# Shruthi-DSP-v03.net
KiCad netlist of a schematic drawn in EAGLE
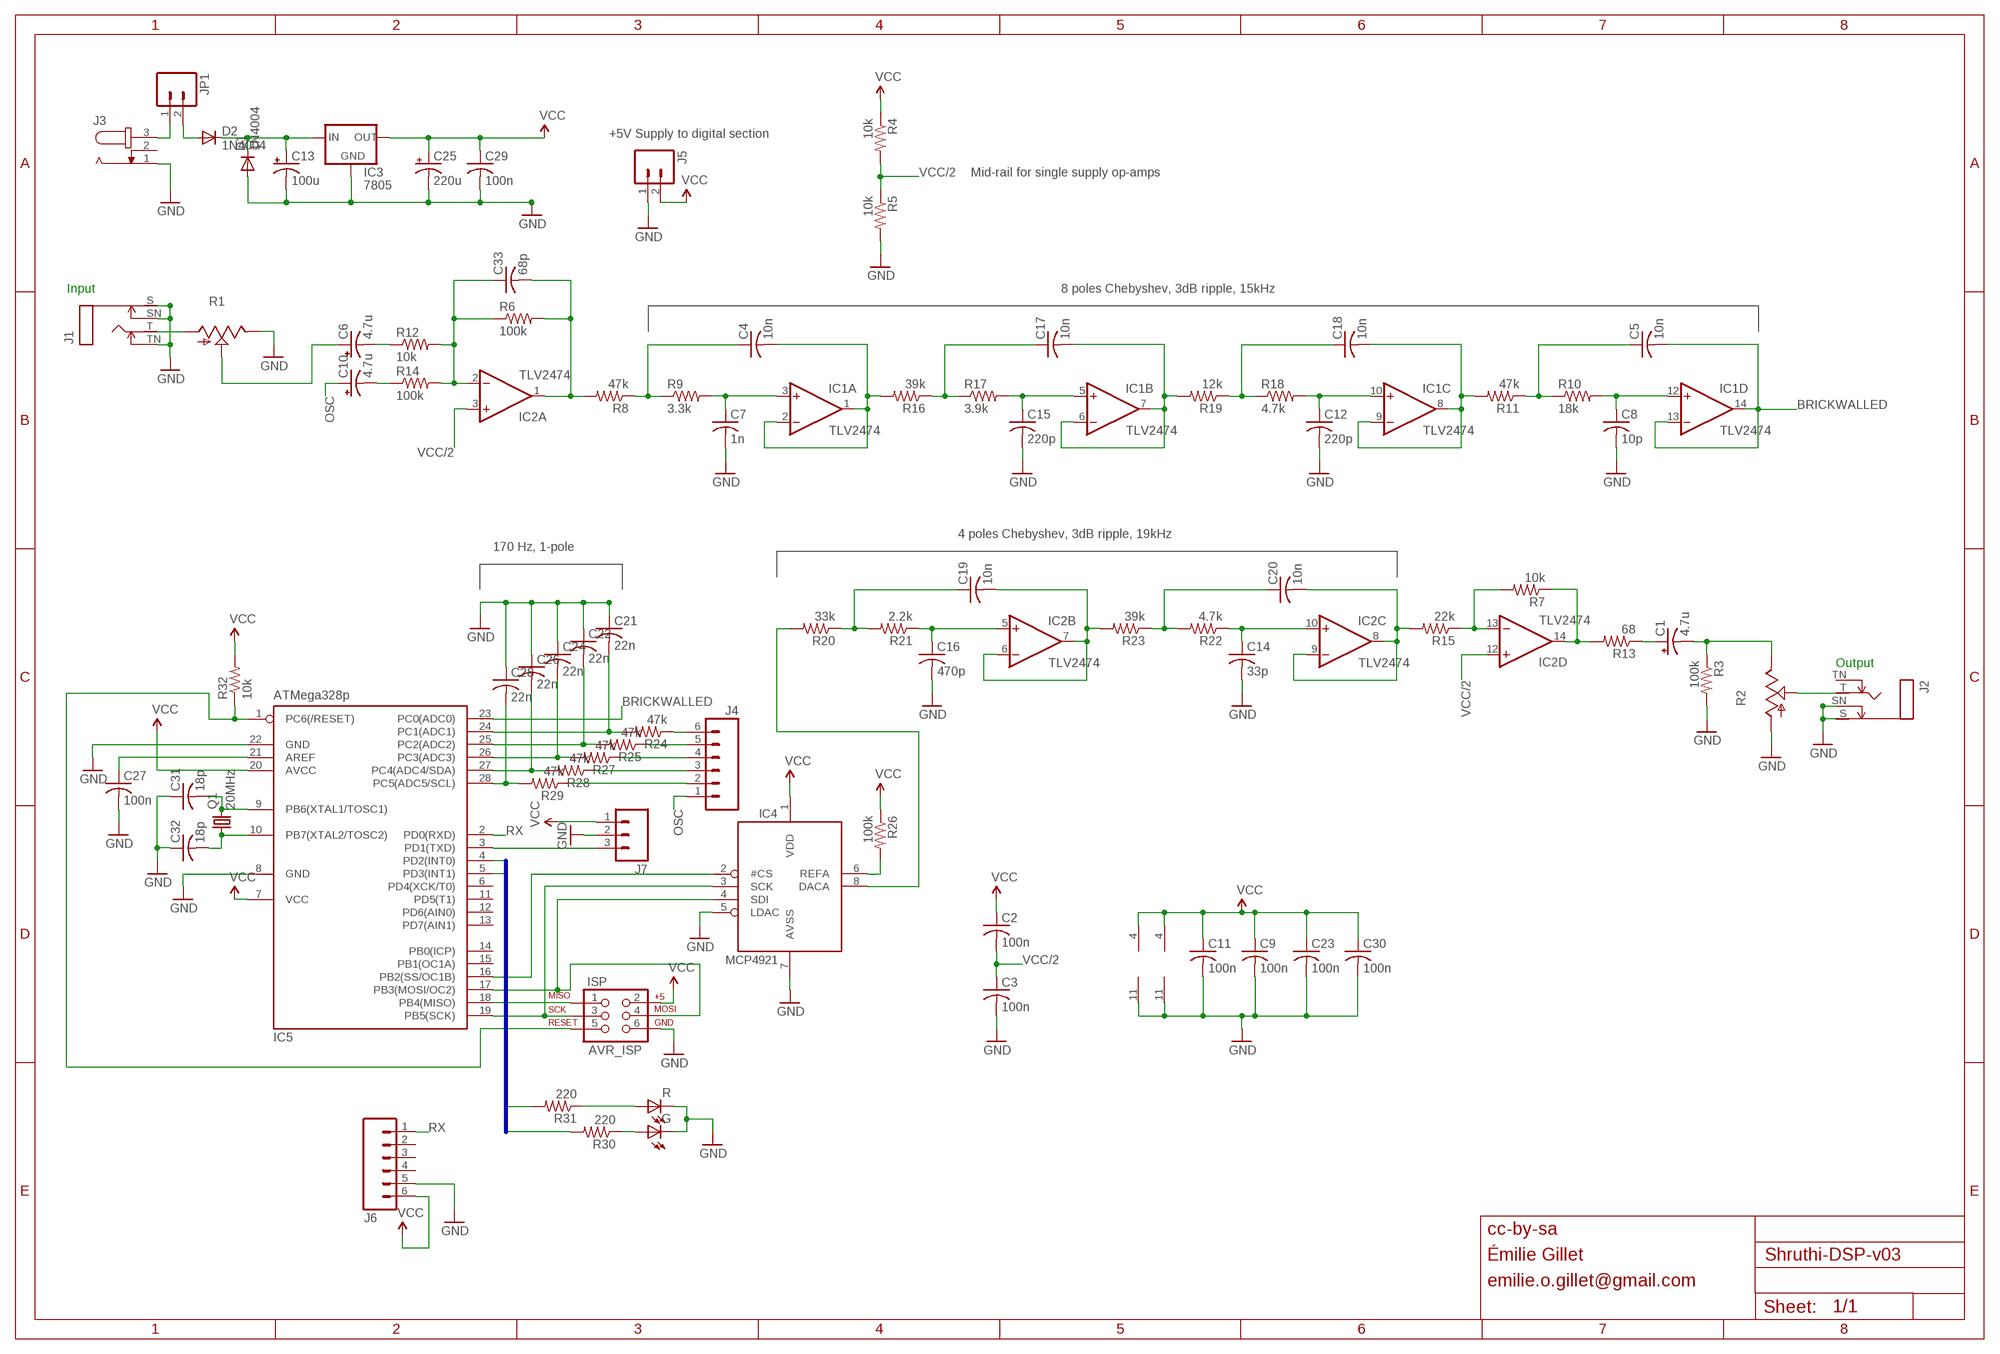
[diagram p0: schematic, sheet 1]

(export (version "E")
  (design (tool "Eeschema 10.0.6"))
  (components
    (comp (ref "C1")
      (value "4.7u")
      (footprint "eagle-import:E2,5-6")
      (libsource (lib "eagle-import") (part "CPOL-USE2.5-6"))
    )
    (comp (ref "C2")
      (value "100n")
      (footprint "eagle-import:C025-024X044")
      (libsource (lib "eagle-import") (part "C-US025-024X044"))
    )
    (comp (ref "C3")
      (value "100n")
      (footprint "eagle-import:C025-024X044")
      (libsource (lib "eagle-import") (part "C-US025-024X044"))
    )
    (comp (ref "C4")
      (value "10n")
      (footprint "eagle-import:C050-025X075")
      (libsource (lib "eagle-import") (part "C-US050-025X075"))
    )
    (comp (ref "C5")
      (value "10n")
      (footprint "eagle-import:C050-025X075")
      (libsource (lib "eagle-import") (part "C-US050-025X075"))
    )
    (comp (ref "C6")
      (value "4.7u")
      (footprint "eagle-import:E2,5-6")
      (libsource (lib "eagle-import") (part "CPOL-USE2.5-6"))
    )
    (comp (ref "C7")
      (value "1n")
      (footprint "eagle-import:C025-025X050")
      (libsource (lib "eagle-import") (part "C-US025-025X050"))
    )
    (comp (ref "C8")
      (value "10p")
      (footprint "eagle-import:C025-025X050")
      (libsource (lib "eagle-import") (part "C-US025-025X050"))
    )
    (comp (ref "C9")
      (value "100n")
      (footprint "eagle-import:C025-025X050")
      (libsource (lib "eagle-import") (part "C-US025-025X050"))
    )
    (comp (ref "C10")
      (value "4.7u")
      (footprint "eagle-import:E2,5-6")
      (libsource (lib "eagle-import") (part "CPOL-USE2.5-6"))
    )
    (comp (ref "C11")
      (value "100n")
      (footprint "eagle-import:C025-025X050")
      (libsource (lib "eagle-import") (part "C-US025-025X050"))
    )
    (comp (ref "C12")
      (value "220p")
      (footprint "eagle-import:C025-025X050")
      (libsource (lib "eagle-import") (part "C-US025-025X050"))
    )
    (comp (ref "C13")
      (value "100u")
      (footprint "eagle-import:E2,5-7")
      (libsource (lib "eagle-import") (part "CPOL-USE2.5-7"))
    )
    (comp (ref "C14")
      (value "33p")
      (footprint "eagle-import:C025-025X050")
      (libsource (lib "eagle-import") (part "C-US025-025X050"))
    )
    (comp (ref "C15")
      (value "220p")
      (footprint "eagle-import:C025-025X050")
      (libsource (lib "eagle-import") (part "C-US025-025X050"))
    )
    (comp (ref "C16")
      (value "470p")
      (footprint "eagle-import:C025-025X050")
      (libsource (lib "eagle-import") (part "C-US025-025X050"))
    )
    (comp (ref "C17")
      (value "10n")
      (footprint "eagle-import:C050-025X075")
      (libsource (lib "eagle-import") (part "C-US050-025X075"))
    )
    (comp (ref "C18")
      (value "10n")
      (footprint "eagle-import:C050-025X075")
      (libsource (lib "eagle-import") (part "C-US050-025X075"))
    )
    (comp (ref "C19")
      (value "10n")
      (footprint "eagle-import:C050-025X075")
      (libsource (lib "eagle-import") (part "C-US050-025X075"))
    )
    (comp (ref "C20")
      (value "10n")
      (footprint "eagle-import:C050-025X075")
      (libsource (lib "eagle-import") (part "C-US050-025X075"))
    )
    (comp (ref "C21")
      (value "22n")
      (footprint "eagle-import:C050-025X075")
      (libsource (lib "eagle-import") (part "C-US050-025X075"))
    )
    (comp (ref "C22")
      (value "22n")
      (footprint "eagle-import:C050-025X075")
      (libsource (lib "eagle-import") (part "C-US050-025X075"))
    )
    (comp (ref "C23")
      (value "100n")
      (footprint "eagle-import:C025-025X050")
      (libsource (lib "eagle-import") (part "C-US025-025X050"))
    )
    (comp (ref "C24")
      (value "22n")
      (footprint "eagle-import:C050-025X075")
      (libsource (lib "eagle-import") (part "C-US050-025X075"))
    )
    (comp (ref "C25")
      (value "220u")
      (footprint "eagle-import:E5-10,5")
      (libsource (lib "eagle-import") (part "CPOL-USE5-10.5"))
    )
    (comp (ref "C26")
      (value "22n")
      (footprint "eagle-import:C050-025X075")
      (libsource (lib "eagle-import") (part "C-US050-025X075"))
    )
    (comp (ref "C27")
      (value "100n")
      (footprint "eagle-import:C025-025X050")
      (libsource (lib "eagle-import") (part "C-US025-025X050"))
    )
    (comp (ref "C28")
      (value "22n")
      (footprint "eagle-import:C050-025X075")
      (libsource (lib "eagle-import") (part "C-US050-025X075"))
    )
    (comp (ref "C29")
      (value "100n")
      (footprint "eagle-import:C025-025X050")
      (libsource (lib "eagle-import") (part "C-US025-025X050"))
    )
    (comp (ref "C30")
      (value "100n")
      (footprint "eagle-import:C025-024X044")
      (libsource (lib "eagle-import") (part "C-US025-024X044"))
    )
    (comp (ref "C31")
      (value "18p")
      (footprint "eagle-import:C025-024X044")
      (libsource (lib "eagle-import") (part "C-US025-024X044"))
    )
    (comp (ref "C32")
      (value "18p")
      (footprint "eagle-import:C025-024X044")
      (libsource (lib "eagle-import") (part "C-US025-024X044"))
    )
    (comp (ref "C33")
      (value "68p")
      (footprint "eagle-import:C025-025X050")
      (libsource (lib "eagle-import") (part "C-US025-025X050"))
    )
    (comp (ref "D1")
      (value "1N4004")
      (footprint "eagle-import:DO41-10")
      (libsource (lib "eagle-import") (part "1N4004"))
    )
    (comp (ref "D2")
      (value "1N4004")
      (footprint "eagle-import:DO41-10")
      (libsource (lib "eagle-import") (part "1N4004"))
    )
    (comp (ref "G")
      (value "LED3MM")
      (footprint "eagle-import:LED3MM")
      (libsource (lib "eagle-import") (part "LED3MM"))
    )
    (comp (ref "IC1")
      (value "TLV2474")
      (footprint "eagle-import:DIL14")
      (libsource (lib "eagle-import") (part "TL084P"))
    )
    (comp (ref "IC2")
      (value "TLV2474")
      (footprint "eagle-import:DIL14")
      (libsource (lib "eagle-import") (part "TL084P"))
    )
    (comp (ref "IC3")
      (value "7805")
      (footprint "eagle-import:78XXS")
      (libsource (lib "eagle-import") (part "78XXS"))
    )
    (comp (ref "IC4")
      (value "MCP4921")
      (footprint "eagle-import:DIL08")
      (libsource (lib "eagle-import") (part "MCP4921"))
    )
    (comp (ref "IC5")
      (value "ATMega328p")
      (footprint "eagle-import:DIL28-3")
      (libsource (lib "eagle-import") (part "MEGA8-P"))
    )
    (comp (ref "ISP")
      (value "AVR_ISP")
      (footprint "eagle-import:2X3")
      (libsource (lib "eagle-import") (part "AVR_SPI_PRG_6PTH"))
    )
    (comp (ref "J1")
      (value "MONOSWS")
      (footprint "eagle-import:NMJ4HC-S")
      (libsource (lib "eagle-import") (part "MONOSWS"))
    )
    (comp (ref "J2")
      (value "MONOSWS")
      (footprint "eagle-import:NMJ4HC-S")
      (libsource (lib "eagle-import") (part "MONOSWS"))
    )
    (comp (ref "J3")
      (value "JACK-PLUG2")
      (footprint "eagle-import:SPC4078_BIG_HOLES")
      (libsource (lib "eagle-import") (part "JACK-PLUG2"))
    )
    (comp (ref "J4")
      (value "M06SIP")
      (footprint "eagle-import:1X06")
      (libsource (lib "eagle-import") (part "M06SIP"))
    )
    (comp (ref "J5")
      (value "M02PTH")
      (footprint "eagle-import:1X02")
      (libsource (lib "eagle-import") (part "M02PTH"))
    )
    (comp (ref "J6")
      (value "M06SIP")
      (footprint "eagle-import:1X06")
      (libsource (lib "eagle-import") (part "M06SIP"))
    )
    (comp (ref "J7")
      (value "M03PTH")
      (footprint "eagle-import:1X03")
      (libsource (lib "eagle-import") (part "M03PTH"))
    )
    (comp (ref "JP1")
      (value "M02")
      (footprint "eagle-import:1X02_LONGPADS")
      (libsource (lib "eagle-import") (part "M02"))
    )
    (comp (ref "Q1")
      (value "20MHz")
      (footprint "eagle-import:HC49U-V")
      (libsource (lib "eagle-import") (part "CRYSTALHC49U-V"))
    )
    (comp (ref "R")
      (value "LED3MM")
      (footprint "eagle-import:LED3MM")
      (libsource (lib "eagle-import") (part "LED3MM"))
    )
    (comp (ref "R1")
      (value "POT_USCABLED")
      (footprint "eagle-import:CABLE_POT_6MM")
      (libsource (lib "eagle-import") (part "POT_USCABLED"))
    )
    (comp (ref "R2")
      (value "POT_USCABLED")
      (footprint "eagle-import:CABLE_POT_6MM")
      (libsource (lib "eagle-import") (part "POT_USCABLED"))
    )
    (comp (ref "R3")
      (value "100k")
      (footprint "eagle-import:0204_7")
      (libsource (lib "eagle-import") (part "R-US_0204/7"))
    )
    (comp (ref "R4")
      (value "10k")
      (footprint "eagle-import:0204_7")
      (libsource (lib "eagle-import") (part "R-US_0204/7"))
    )
    (comp (ref "R5")
      (value "10k")
      (footprint "eagle-import:0204_7")
      (libsource (lib "eagle-import") (part "R-US_0204/7"))
    )
    (comp (ref "R6")
      (value "100k")
      (footprint "eagle-import:0204_7")
      (libsource (lib "eagle-import") (part "R-US_0204/7"))
    )
    (comp (ref "R7")
      (value "10k")
      (footprint "eagle-import:0204_7")
      (libsource (lib "eagle-import") (part "R-US_0204/7"))
    )
    (comp (ref "R8")
      (value "47k")
      (footprint "eagle-import:0204_7")
      (libsource (lib "eagle-import") (part "R-US_0204/7"))
    )
    (comp (ref "R9")
      (value "3.3k")
      (footprint "eagle-import:0204_7")
      (libsource (lib "eagle-import") (part "R-US_0204/7"))
    )
    (comp (ref "R10")
      (value "18k")
      (footprint "eagle-import:0204_7")
      (libsource (lib "eagle-import") (part "R-US_0204/7"))
    )
    (comp (ref "R11")
      (value "47k")
      (footprint "eagle-import:0204_7")
      (libsource (lib "eagle-import") (part "R-US_0204/7"))
    )
    (comp (ref "R12")
      (value "10k")
      (footprint "eagle-import:0204_7")
      (libsource (lib "eagle-import") (part "R-US_0204/7"))
    )
    (comp (ref "R13")
      (value "68")
      (footprint "eagle-import:0204_7")
      (libsource (lib "eagle-import") (part "R-US_0204/7"))
    )
    (comp (ref "R14")
      (value "100k")
      (footprint "eagle-import:0204_7")
      (libsource (lib "eagle-import") (part "R-US_0204/7"))
    )
    (comp (ref "R15")
      (value "22k")
      (footprint "eagle-import:0204_7")
      (libsource (lib "eagle-import") (part "R-US_0204/7"))
    )
    (comp (ref "R16")
      (value "39k")
      (footprint "eagle-import:0204_7")
      (libsource (lib "eagle-import") (part "R-US_0204/7"))
    )
    (comp (ref "R17")
      (value "3.9k")
      (footprint "eagle-import:0204_7")
      (libsource (lib "eagle-import") (part "R-US_0204/7"))
    )
    (comp (ref "R18")
      (value "4.7k")
      (footprint "eagle-import:0204_7")
      (libsource (lib "eagle-import") (part "R-US_0204/7"))
    )
    (comp (ref "R19")
      (value "12k")
      (footprint "eagle-import:0204_7")
      (libsource (lib "eagle-import") (part "R-US_0204/7"))
    )
    (comp (ref "R20")
      (value "33k")
      (footprint "eagle-import:0204_7")
      (libsource (lib "eagle-import") (part "R-US_0204/7"))
    )
    (comp (ref "R21")
      (value "2.2k")
      (footprint "eagle-import:0204_7")
      (libsource (lib "eagle-import") (part "R-US_0204/7"))
    )
    (comp (ref "R22")
      (value "4.7k")
      (footprint "eagle-import:0204_7")
      (libsource (lib "eagle-import") (part "R-US_0204/7"))
    )
    (comp (ref "R23")
      (value "39k")
      (footprint "eagle-import:0204_7")
      (libsource (lib "eagle-import") (part "R-US_0204/7"))
    )
    (comp (ref "R24")
      (value "47k")
      (footprint "eagle-import:0204_7")
      (libsource (lib "eagle-import") (part "R-US_0204/7"))
    )
    (comp (ref "R25")
      (value "47k")
      (footprint "eagle-import:0204_7")
      (libsource (lib "eagle-import") (part "R-US_0204/7"))
    )
    (comp (ref "R26")
      (value "100k")
      (footprint "eagle-import:0204_7")
      (libsource (lib "eagle-import") (part "R-US_0204/7"))
    )
    (comp (ref "R27")
      (value "47k")
      (footprint "eagle-import:0204_7")
      (libsource (lib "eagle-import") (part "R-US_0204/7"))
    )
    (comp (ref "R28")
      (value "47k")
      (footprint "eagle-import:0204_7")
      (libsource (lib "eagle-import") (part "R-US_0204/7"))
    )
    (comp (ref "R29")
      (value "47k")
      (footprint "eagle-import:0204_7")
      (libsource (lib "eagle-import") (part "R-US_0204/7"))
    )
    (comp (ref "R30")
      (value "220")
      (footprint "eagle-import:0204_7")
      (libsource (lib "eagle-import") (part "R-US_0204/7"))
    )
    (comp (ref "R31")
      (value "220")
      (footprint "eagle-import:0204_7")
      (libsource (lib "eagle-import") (part "R-US_0204/7"))
    )
    (comp (ref "R32")
      (value "10k")
      (footprint "eagle-import:0204_7")
      (libsource (lib "eagle-import") (part "R-US_0204/7"))
    )
  )
  (nets
    (net (code "1") (name "/BRICKWALLED") (class "Default")
      (node (ref "C5") (pin "2") (pinfunction "2_2") (pintype "passive"))
      (node (ref "IC1") (pin "13") (pinfunction "-IN_13") (pintype "input"))
      (node (ref "IC1") (pin "14") (pinfunction "OUT_14") (pintype "output"))
      (node (ref "IC5") (pin "23") (pinfunction "PC0(ADC0)_23") (pintype "bidirectional"))
    )
    (net (code "2") (name "/LEDS0") (class "Default")
      (node (ref "IC5") (pin "4") (pinfunction "PD2(INT0)_4") (pintype "bidirectional"))
      (node (ref "R31") (pin "2") (pinfunction "2_2") (pintype "passive"))
    )
    (net (code "3") (name "/LEDS1") (class "Default")
      (node (ref "IC5") (pin "5") (pinfunction "PD3(INT1)_5") (pintype "bidirectional"))
      (node (ref "R30") (pin "2") (pinfunction "2_2") (pintype "passive"))
    )
    (net (code "4") (name "/OSC") (class "Default")
      (node (ref "C10") (pin "+") (pinfunction "+_+") (pintype "passive"))
      (node (ref "J4") (pin "1") (pinfunction "1_1") (pintype "passive"))
    )
    (net (code "5") (name "/RX") (class "Default")
      (node (ref "IC5") (pin "2") (pinfunction "PD0(RXD)_2") (pintype "bidirectional"))
      (node (ref "J6") (pin "1") (pinfunction "1_1") (pintype "passive"))
    )
    (net (code "6") (name "/VCC{slash}2") (class "Default")
      (node (ref "C2") (pin "2") (pinfunction "2_2") (pintype "passive"))
      (node (ref "C3") (pin "1") (pinfunction "1_1") (pintype "passive"))
      (node (ref "IC2") (pin "12") (pinfunction "+IN_12") (pintype "input"))
      (node (ref "IC2") (pin "3") (pinfunction "+IN_3") (pintype "input"))
      (node (ref "R4") (pin "2") (pinfunction "2_2") (pintype "passive"))
      (node (ref "R5") (pin "1") (pinfunction "1_1") (pintype "passive"))
    )
    (net (code "7") (name "GND") (class "Default")
      (node (ref "C11") (pin "2") (pinfunction "2_2") (pintype "passive"))
      (node (ref "C12") (pin "2") (pinfunction "2_2") (pintype "passive"))
      (node (ref "C13") (pin "-") (pinfunction "-_-") (pintype "passive"))
      (node (ref "C14") (pin "2") (pinfunction "2_2") (pintype "passive"))
      (node (ref "C15") (pin "2") (pinfunction "2_2") (pintype "passive"))
      (node (ref "C16") (pin "2") (pinfunction "2_2") (pintype "passive"))
      (node (ref "C21") (pin "1") (pinfunction "1_1") (pintype "passive"))
      (node (ref "C22") (pin "1") (pinfunction "1_1") (pintype "passive"))
      (node (ref "C23") (pin "2") (pinfunction "2_2") (pintype "passive"))
      (node (ref "C24") (pin "1") (pinfunction "1_1") (pintype "passive"))
      (node (ref "C25") (pin "-") (pinfunction "-_-") (pintype "passive"))
      (node (ref "C26") (pin "1") (pinfunction "1_1") (pintype "passive"))
      (node (ref "C27") (pin "2") (pinfunction "2_2") (pintype "passive"))
      (node (ref "C28") (pin "1") (pinfunction "1_1") (pintype "passive"))
      (node (ref "C29") (pin "2") (pinfunction "2_2") (pintype "passive"))
      (node (ref "C3") (pin "2") (pinfunction "2_2") (pintype "passive"))
      (node (ref "C30") (pin "2") (pinfunction "2_2") (pintype "passive"))
      (node (ref "C31") (pin "1") (pinfunction "1_1") (pintype "passive"))
      (node (ref "C32") (pin "1") (pinfunction "1_1") (pintype "passive"))
      (node (ref "C7") (pin "2") (pinfunction "2_2") (pintype "passive"))
      (node (ref "C8") (pin "2") (pinfunction "2_2") (pintype "passive"))
      (node (ref "C9") (pin "2") (pinfunction "2_2") (pintype "passive"))
      (node (ref "D1") (pin "A") (pinfunction "A_A") (pintype "passive"))
      (node (ref "G") (pin "K") (pinfunction "C_K") (pintype "passive"))
      (node (ref "IC1") (pin "11") (pinfunction "V-_11") (pintype "power_in"))
      (node (ref "IC2") (pin "11") (pinfunction "V-_11") (pintype "power_in"))
      (node (ref "IC3") (pin "GND") (pinfunction "GND_GND") (pintype "input"))
      (node (ref "IC4") (pin "5") (pinfunction "LDAC_5") (pintype "input"))
      (node (ref "IC4") (pin "7") (pinfunction "AVSS_7") (pintype "power_in"))
      (node (ref "IC5") (pin "22") (pinfunction "GND_22") (pintype "power_in"))
      (node (ref "IC5") (pin "8") (pinfunction "GND_8") (pintype "power_in"))
      (node (ref "ISP") (pin "6") (pinfunction "6_6") (pintype "passive"))
      (node (ref "J1") (pin "S") (pinfunction "S_S") (pintype "passive"))
      (node (ref "J1") (pin "SN") (pinfunction "SN_SN") (pintype "passive"))
      (node (ref "J1") (pin "TN") (pinfunction "TN_TN") (pintype "passive"))
      (node (ref "J2") (pin "S") (pinfunction "S_S") (pintype "passive"))
      (node (ref "J2") (pin "SN") (pinfunction "SN_SN") (pintype "passive"))
      (node (ref "J3") (pin "1") (pinfunction "1_1") (pintype "passive"))
      (node (ref "J5") (pin "1") (pinfunction "1_1") (pintype "passive"))
      (node (ref "J6") (pin "5") (pinfunction "5_5") (pintype "passive"))
      (node (ref "J7") (pin "2") (pinfunction "2_2") (pintype "passive"))
      (node (ref "R") (pin "K") (pinfunction "C_K") (pintype "passive"))
      (node (ref "R1") (pin "E") (pinfunction "E_E") (pintype "passive"))
      (node (ref "R2") (pin "A") (pinfunction "A_A") (pintype "passive"))
      (node (ref "R3") (pin "2") (pinfunction "2_2") (pintype "passive"))
      (node (ref "R5") (pin "2") (pinfunction "2_2") (pintype "passive"))
    )
    (net (code "8") (name "Net-(C1-Pad+)") (class "Default")
      (node (ref "C1") (pin "+") (pinfunction "+_+") (pintype "passive"))
      (node (ref "R13") (pin "1") (pinfunction "1_1") (pintype "passive"))
    )
    (net (code "9") (name "Net-(C1-Pad-)") (class "Default")
      (node (ref "C1") (pin "-") (pinfunction "-_-") (pintype "passive"))
      (node (ref "R2") (pin "E") (pinfunction "E_E") (pintype "passive"))
      (node (ref "R3") (pin "1") (pinfunction "1_1") (pintype "passive"))
    )
    (net (code "10") (name "Net-(C4-Pad1)") (class "Default")
      (node (ref "C4") (pin "1") (pinfunction "1_1") (pintype "passive"))
      (node (ref "R8") (pin "1") (pinfunction "1_1") (pintype "passive"))
      (node (ref "R9") (pin "1") (pinfunction "1_1") (pintype "passive"))
    )
    (net (code "11") (name "Net-(C5-Pad1)") (class "Default")
      (node (ref "C5") (pin "1") (pinfunction "1_1") (pintype "passive"))
      (node (ref "R10") (pin "1") (pinfunction "1_1") (pintype "passive"))
      (node (ref "R11") (pin "1") (pinfunction "1_1") (pintype "passive"))
    )
    (net (code "12") (name "Net-(C6-Pad+)") (class "Default")
      (node (ref "C6") (pin "+") (pinfunction "+_+") (pintype "passive"))
      (node (ref "R1") (pin "S") (pinfunction "S_S") (pintype "passive"))
    )
    (net (code "13") (name "Net-(C6-Pad-)") (class "Default")
      (node (ref "C6") (pin "-") (pinfunction "-_-") (pintype "passive"))
      (node (ref "R12") (pin "1") (pinfunction "1_1") (pintype "passive"))
    )
    (net (code "14") (name "Net-(C10-Pad-)") (class "Default")
      (node (ref "C10") (pin "-") (pinfunction "-_-") (pintype "passive"))
      (node (ref "R14") (pin "1") (pinfunction "1_1") (pintype "passive"))
    )
    (net (code "15") (name "Net-(C13-Pad+)") (class "Default")
      (node (ref "C13") (pin "+") (pinfunction "+_+") (pintype "passive"))
      (node (ref "D1") (pin "C") (pinfunction "C_C") (pintype "passive"))
      (node (ref "D2") (pin "C") (pinfunction "C_C") (pintype "passive"))
      (node (ref "IC3") (pin "IN") (pinfunction "IN_IN") (pintype "input"))
    )
    (net (code "16") (name "Net-(C17-Pad1)") (class "Default")
      (node (ref "C17") (pin "1") (pinfunction "1_1") (pintype "passive"))
      (node (ref "R16") (pin "1") (pinfunction "1_1") (pintype "passive"))
      (node (ref "R17") (pin "1") (pinfunction "1_1") (pintype "passive"))
    )
    (net (code "17") (name "Net-(C18-Pad1)") (class "Default")
      (node (ref "C18") (pin "1") (pinfunction "1_1") (pintype "passive"))
      (node (ref "R18") (pin "1") (pinfunction "1_1") (pintype "passive"))
      (node (ref "R19") (pin "1") (pinfunction "1_1") (pintype "passive"))
    )
    (net (code "18") (name "Net-(C19-Pad1)") (class "Default")
      (node (ref "C19") (pin "1") (pinfunction "1_1") (pintype "passive"))
      (node (ref "R20") (pin "1") (pinfunction "1_1") (pintype "passive"))
      (node (ref "R21") (pin "2") (pinfunction "2_2") (pintype "passive"))
    )
    (net (code "19") (name "Net-(C20-Pad1)") (class "Default")
      (node (ref "C20") (pin "1") (pinfunction "1_1") (pintype "passive"))
      (node (ref "R22") (pin "2") (pinfunction "2_2") (pintype "passive"))
      (node (ref "R23") (pin "1") (pinfunction "1_1") (pintype "passive"))
    )
    (net (code "20") (name "Net-(D2-PadA)") (class "Default")
      (node (ref "D2") (pin "A") (pinfunction "A_A") (pintype "passive"))
      (node (ref "JP1") (pin "2") (pinfunction "2_2") (pintype "passive"))
    )
    (net (code "21") (name "Net-(G-PadA)") (class "Default")
      (node (ref "G") (pin "A") (pinfunction "A_A") (pintype "passive"))
      (node (ref "R30") (pin "1") (pinfunction "1_1") (pintype "passive"))
    )
    (net (code "22") (name "Net-(IC1A-+IN)") (class "Default")
      (node (ref "C7") (pin "1") (pinfunction "1_1") (pintype "passive"))
      (node (ref "IC1") (pin "3") (pinfunction "+IN_3") (pintype "input"))
      (node (ref "R9") (pin "2") (pinfunction "2_2") (pintype "passive"))
    )
    (net (code "23") (name "Net-(IC1A--IN)") (class "Default")
      (node (ref "C4") (pin "2") (pinfunction "2_2") (pintype "passive"))
      (node (ref "IC1") (pin "1") (pinfunction "OUT_1") (pintype "output"))
      (node (ref "IC1") (pin "2") (pinfunction "-IN_2") (pintype "input"))
      (node (ref "R16") (pin "2") (pinfunction "2_2") (pintype "passive"))
    )
    (net (code "24") (name "Net-(IC1B-+IN)") (class "Default")
      (node (ref "C15") (pin "1") (pinfunction "1_1") (pintype "passive"))
      (node (ref "IC1") (pin "5") (pinfunction "+IN_5") (pintype "input"))
      (node (ref "R17") (pin "2") (pinfunction "2_2") (pintype "passive"))
    )
    (net (code "25") (name "Net-(IC1B--IN)") (class "Default")
      (node (ref "C17") (pin "2") (pinfunction "2_2") (pintype "passive"))
      (node (ref "IC1") (pin "6") (pinfunction "-IN_6") (pintype "input"))
      (node (ref "IC1") (pin "7") (pinfunction "OUT_7") (pintype "output"))
      (node (ref "R19") (pin "2") (pinfunction "2_2") (pintype "passive"))
    )
    (net (code "26") (name "Net-(IC1C-+IN)") (class "Default")
      (node (ref "C12") (pin "1") (pinfunction "1_1") (pintype "passive"))
      (node (ref "IC1") (pin "10") (pinfunction "+IN_10") (pintype "input"))
      (node (ref "R18") (pin "2") (pinfunction "2_2") (pintype "passive"))
    )
    (net (code "27") (name "Net-(IC1C--IN)") (class "Default")
      (node (ref "C18") (pin "2") (pinfunction "2_2") (pintype "passive"))
      (node (ref "IC1") (pin "8") (pinfunction "OUT_8") (pintype "output"))
      (node (ref "IC1") (pin "9") (pinfunction "-IN_9") (pintype "input"))
      (node (ref "R11") (pin "2") (pinfunction "2_2") (pintype "passive"))
    )
    (net (code "28") (name "Net-(IC1D-+IN)") (class "Default")
      (node (ref "C8") (pin "1") (pinfunction "1_1") (pintype "passive"))
      (node (ref "IC1") (pin "12") (pinfunction "+IN_12") (pintype "input"))
      (node (ref "R10") (pin "2") (pinfunction "2_2") (pintype "passive"))
    )
    (net (code "29") (name "Net-(IC2A--IN)") (class "Default")
      (node (ref "C33") (pin "1") (pinfunction "1_1") (pintype "passive"))
      (node (ref "IC2") (pin "2") (pinfunction "-IN_2") (pintype "input"))
      (node (ref "R12") (pin "2") (pinfunction "2_2") (pintype "passive"))
      (node (ref "R14") (pin "2") (pinfunction "2_2") (pintype "passive"))
      (node (ref "R6") (pin "1") (pinfunction "1_1") (pintype "passive"))
    )
    (net (code "30") (name "Net-(IC2A-OUT)") (class "Default")
      (node (ref "C33") (pin "2") (pinfunction "2_2") (pintype "passive"))
      (node (ref "IC2") (pin "1") (pinfunction "OUT_1") (pintype "output"))
      (node (ref "R6") (pin "2") (pinfunction "2_2") (pintype "passive"))
      (node (ref "R8") (pin "2") (pinfunction "2_2") (pintype "passive"))
    )
    (net (code "31") (name "Net-(IC2B-+IN)") (class "Default")
      (node (ref "C16") (pin "1") (pinfunction "1_1") (pintype "passive"))
      (node (ref "IC2") (pin "5") (pinfunction "+IN_5") (pintype "input"))
      (node (ref "R21") (pin "1") (pinfunction "1_1") (pintype "passive"))
    )
    (net (code "32") (name "Net-(IC2B--IN)") (class "Default")
      (node (ref "C19") (pin "2") (pinfunction "2_2") (pintype "passive"))
      (node (ref "IC2") (pin "6") (pinfunction "-IN_6") (pintype "input"))
      (node (ref "IC2") (pin "7") (pinfunction "OUT_7") (pintype "output"))
      (node (ref "R23") (pin "2") (pinfunction "2_2") (pintype "passive"))
    )
    (net (code "33") (name "Net-(IC2C-+IN)") (class "Default")
      (node (ref "C14") (pin "1") (pinfunction "1_1") (pintype "passive"))
      (node (ref "IC2") (pin "10") (pinfunction "+IN_10") (pintype "input"))
      (node (ref "R22") (pin "1") (pinfunction "1_1") (pintype "passive"))
    )
    (net (code "34") (name "Net-(IC2C--IN)") (class "Default")
      (node (ref "C20") (pin "2") (pinfunction "2_2") (pintype "passive"))
      (node (ref "IC2") (pin "8") (pinfunction "OUT_8") (pintype "output"))
      (node (ref "IC2") (pin "9") (pinfunction "-IN_9") (pintype "input"))
      (node (ref "R15") (pin "2") (pinfunction "2_2") (pintype "passive"))
    )
    (net (code "35") (name "Net-(IC2D--IN)") (class "Default")
      (node (ref "IC2") (pin "13") (pinfunction "-IN_13") (pintype "input"))
      (node (ref "R15") (pin "1") (pinfunction "1_1") (pintype "passive"))
      (node (ref "R7") (pin "2") (pinfunction "2_2") (pintype "passive"))
    )
    (net (code "36") (name "Net-(IC2D-OUT)") (class "Default")
      (node (ref "IC2") (pin "14") (pinfunction "OUT_14") (pintype "output"))
      (node (ref "R13") (pin "2") (pinfunction "2_2") (pintype "passive"))
      (node (ref "R7") (pin "1") (pinfunction "1_1") (pintype "passive"))
    )
    (net (code "37") (name "Net-(IC4-#CS)") (class "Default")
      (node (ref "IC4") (pin "2") (pinfunction "#CS_2") (pintype "input"))
      (node (ref "IC5") (pin "16") (pinfunction "PB2(SS/OC1B)_16") (pintype "bidirectional"))
    )
    (net (code "38") (name "Net-(IC4-DACA)") (class "Default")
      (node (ref "IC4") (pin "8") (pinfunction "DACA_8") (pintype "output"))
      (node (ref "R20") (pin "2") (pinfunction "2_2") (pintype "passive"))
    )
    (net (code "39") (name "Net-(IC4-REFA)") (class "Default")
      (node (ref "IC4") (pin "6") (pinfunction "REFA_6") (pintype "input"))
      (node (ref "R26") (pin "2") (pinfunction "2_2") (pintype "passive"))
    )
    (net (code "40") (name "Net-(IC4-SCK)") (class "Default")
      (node (ref "IC4") (pin "3") (pinfunction "SCK_3") (pintype "input"))
      (node (ref "IC5") (pin "19") (pinfunction "PB5(SCK)_19") (pintype "bidirectional"))
      (node (ref "ISP") (pin "3") (pinfunction "3_3") (pintype "passive"))
    )
    (net (code "41") (name "Net-(IC4-SDI)") (class "Default")
      (node (ref "IC4") (pin "4") (pinfunction "SDI_4") (pintype "input"))
      (node (ref "IC5") (pin "17") (pinfunction "PB3(MOSI/OC2)_17") (pintype "bidirectional"))
      (node (ref "ISP") (pin "4") (pinfunction "4_4") (pintype "passive"))
    )
    (net (code "42") (name "Net-(IC5-AREF)") (class "Default")
      (node (ref "C27") (pin "1") (pinfunction "1_1") (pintype "passive"))
      (node (ref "IC5") (pin "21") (pinfunction "AREF_21") (pintype "passive"))
    )
    (net (code "43") (name "Net-(IC5-PB4(MISO))") (class "Default")
      (node (ref "IC5") (pin "18") (pinfunction "PB4(MISO)_18") (pintype "bidirectional"))
      (node (ref "ISP") (pin "1") (pinfunction "1_1") (pintype "passive"))
    )
    (net (code "44") (name "Net-(IC5-PB6(XTAL1{slash}TOSC1))") (class "Default")
      (node (ref "C31") (pin "2") (pinfunction "2_2") (pintype "passive"))
      (node (ref "IC5") (pin "9") (pinfunction "PB6(XTAL1/TOSC1)_9") (pintype "bidirectional"))
      (node (ref "Q1") (pin "2") (pinfunction "2_2") (pintype "passive"))
    )
    (net (code "45") (name "Net-(IC5-PB7(XTAL2{slash}TOSC2))") (class "Default")
      (node (ref "C32") (pin "2") (pinfunction "2_2") (pintype "passive"))
      (node (ref "IC5") (pin "10") (pinfunction "PB7(XTAL2/TOSC2)_10") (pintype "bidirectional"))
      (node (ref "Q1") (pin "1") (pinfunction "1_1") (pintype "passive"))
    )
    (net (code "46") (name "Net-(IC5-PC1(ADC1))") (class "Default")
      (node (ref "C21") (pin "2") (pinfunction "2_2") (pintype "passive"))
      (node (ref "IC5") (pin "24") (pinfunction "PC1(ADC1)_24") (pintype "bidirectional"))
      (node (ref "R24") (pin "2") (pinfunction "2_2") (pintype "passive"))
    )
    (net (code "47") (name "Net-(IC5-PC2(ADC2))") (class "Default")
      (node (ref "C22") (pin "2") (pinfunction "2_2") (pintype "passive"))
      (node (ref "IC5") (pin "25") (pinfunction "PC2(ADC2)_25") (pintype "bidirectional"))
      (node (ref "R25") (pin "2") (pinfunction "2_2") (pintype "passive"))
    )
    (net (code "48") (name "Net-(IC5-PC3(ADC3))") (class "Default")
      (node (ref "C24") (pin "2") (pinfunction "2_2") (pintype "passive"))
      (node (ref "IC5") (pin "26") (pinfunction "PC3(ADC3)_26") (pintype "bidirectional"))
      (node (ref "R27") (pin "2") (pinfunction "2_2") (pintype "passive"))
    )
    (net (code "49") (name "Net-(IC5-PC4(ADC4{slash}SDA))") (class "Default")
      (node (ref "C26") (pin "2") (pinfunction "2_2") (pintype "passive"))
      (node (ref "IC5") (pin "27") (pinfunction "PC4(ADC4/SDA)_27") (pintype "bidirectional"))
      (node (ref "R28") (pin "2") (pinfunction "2_2") (pintype "passive"))
    )
    (net (code "50") (name "Net-(IC5-PC5(ADC5{slash}SCL))") (class "Default")
      (node (ref "C28") (pin "2") (pinfunction "2_2") (pintype "passive"))
      (node (ref "IC5") (pin "28") (pinfunction "PC5(ADC5/SCL)_28") (pintype "bidirectional"))
      (node (ref "R29") (pin "2") (pinfunction "2_2") (pintype "passive"))
    )
    (net (code "51") (name "Net-(IC5-PC6({slash}RESET))") (class "Default")
      (node (ref "IC5") (pin "1") (pinfunction "PC6(/RESET)_1") (pintype "bidirectional"))
      (node (ref "ISP") (pin "5") (pinfunction "5_5") (pintype "passive"))
      (node (ref "R32") (pin "1") (pinfunction "1_1") (pintype "passive"))
    )
    (net (code "52") (name "Net-(IC5-PD1(TXD))") (class "Default")
      (node (ref "IC5") (pin "3") (pinfunction "PD1(TXD)_3") (pintype "bidirectional"))
      (node (ref "J7") (pin "3") (pinfunction "3_3") (pintype "passive"))
    )
    (net (code "53") (name "Net-(J1-PadT)") (class "Default")
      (node (ref "J1") (pin "T") (pinfunction "T_T") (pintype "passive"))
      (node (ref "R1") (pin "A") (pinfunction "A_A") (pintype "passive"))
    )
    (net (code "54") (name "Net-(J2-PadT)") (class "Default")
      (node (ref "J2") (pin "T") (pinfunction "T_T") (pintype "passive"))
      (node (ref "R2") (pin "S") (pinfunction "S_S") (pintype "passive"))
    )
    (net (code "55") (name "Net-(J3-Pad3)") (class "Default")
      (node (ref "J3") (pin "3") (pinfunction "3_3") (pintype "passive"))
      (node (ref "JP1") (pin "1") (pinfunction "1_1") (pintype "passive"))
    )
    (net (code "56") (name "Net-(J4-Pad2)") (class "Default")
      (node (ref "J4") (pin "2") (pinfunction "2_2") (pintype "passive"))
      (node (ref "R29") (pin "1") (pinfunction "1_1") (pintype "passive"))
    )
    (net (code "57") (name "Net-(J4-Pad3)") (class "Default")
      (node (ref "J4") (pin "3") (pinfunction "3_3") (pintype "passive"))
      (node (ref "R28") (pin "1") (pinfunction "1_1") (pintype "passive"))
    )
    (net (code "58") (name "Net-(J4-Pad4)") (class "Default")
      (node (ref "J4") (pin "4") (pinfunction "4_4") (pintype "passive"))
      (node (ref "R27") (pin "1") (pinfunction "1_1") (pintype "passive"))
    )
    (net (code "59") (name "Net-(J4-Pad5)") (class "Default")
      (node (ref "J4") (pin "5") (pinfunction "5_5") (pintype "passive"))
      (node (ref "R25") (pin "1") (pinfunction "1_1") (pintype "passive"))
    )
    (net (code "60") (name "Net-(J4-Pad6)") (class "Default")
      (node (ref "J4") (pin "6") (pinfunction "6_6") (pintype "passive"))
      (node (ref "R24") (pin "1") (pinfunction "1_1") (pintype "passive"))
    )
    (net (code "61") (name "Net-(R-PadA)") (class "Default")
      (node (ref "R") (pin "A") (pinfunction "A_A") (pintype "passive"))
      (node (ref "R31") (pin "1") (pinfunction "1_1") (pintype "passive"))
    )
    (net (code "62") (name "VCC") (class "Default")
      (node (ref "C11") (pin "1") (pinfunction "1_1") (pintype "passive"))
      (node (ref "C2") (pin "1") (pinfunction "1_1") (pintype "passive"))
      (node (ref "C23") (pin "1") (pinfunction "1_1") (pintype "passive"))
      (node (ref "C25") (pin "+") (pinfunction "+_+") (pintype "passive"))
      (node (ref "C29") (pin "1") (pinfunction "1_1") (pintype "passive"))
      (node (ref "C30") (pin "1") (pinfunction "1_1") (pintype "passive"))
      (node (ref "C9") (pin "1") (pinfunction "1_1") (pintype "passive"))
      (node (ref "IC1") (pin "4") (pinfunction "V+_4") (pintype "power_in"))
      (node (ref "IC2") (pin "4") (pinfunction "V+_4") (pintype "power_in"))
      (node (ref "IC3") (pin "OUT") (pinfunction "OUT_OUT") (pintype "passive"))
      (node (ref "IC4") (pin "1") (pinfunction "VDD_1") (pintype "power_in"))
      (node (ref "IC5") (pin "20") (pinfunction "AVCC_20") (pintype "power_in"))
      (node (ref "IC5") (pin "7") (pinfunction "VCC_7") (pintype "power_in"))
      (node (ref "ISP") (pin "2") (pinfunction "2_2") (pintype "passive"))
      (node (ref "J5") (pin "2") (pinfunction "2_2") (pintype "passive"))
      (node (ref "J6") (pin "6") (pinfunction "6_6") (pintype "passive"))
      (node (ref "J7") (pin "1") (pinfunction "1_1") (pintype "passive"))
      (node (ref "R26") (pin "1") (pinfunction "1_1") (pintype "passive"))
      (node (ref "R32") (pin "2") (pinfunction "2_2") (pintype "passive"))
      (node (ref "R4") (pin "1") (pinfunction "1_1") (pintype "passive"))
    )
    (net (code "63") (name "unconnected-(IC5-PB0(ICP)-Pad14)") (class "Default")
      (node (ref "IC5") (pin "14") (pinfunction "PB0(ICP)_14") (pintype "bidirectional"))
    )
    (net (code "64") (name "unconnected-(IC5-PB1(OC1A)-Pad15)") (class "Default")
      (node (ref "IC5") (pin "15") (pinfunction "PB1(OC1A)_15") (pintype "bidirectional"))
    )
    (net (code "65") (name "unconnected-(IC5-PD4(XCK{slash}T0)-Pad6)") (class "Default")
      (node (ref "IC5") (pin "6") (pinfunction "PD4(XCK/T0)_6") (pintype "bidirectional"))
    )
    (net (code "66") (name "unconnected-(IC5-PD5(T1)-Pad11)") (class "Default")
      (node (ref "IC5") (pin "11") (pinfunction "PD5(T1)_11") (pintype "bidirectional"))
    )
    (net (code "67") (name "unconnected-(IC5-PD6(AIN0)-Pad12)") (class "Default")
      (node (ref "IC5") (pin "12") (pinfunction "PD6(AIN0)_12") (pintype "bidirectional"))
    )
    (net (code "68") (name "unconnected-(IC5-PD7(AIN1)-Pad13)") (class "Default")
      (node (ref "IC5") (pin "13") (pinfunction "PD7(AIN1)_13") (pintype "bidirectional"))
    )
    (net (code "69") (name "unconnected-(J2-PadTN)") (class "Default")
      (node (ref "J2") (pin "TN") (pinfunction "TN_TN") (pintype "passive"))
    )
    (net (code "70") (name "unconnected-(J3-Pad2)") (class "Default")
      (node (ref "J3") (pin "2") (pinfunction "2_2") (pintype "passive"))
    )
    (net (code "71") (name "unconnected-(J6-Pad2)") (class "Default")
      (node (ref "J6") (pin "2") (pinfunction "2_2") (pintype "passive"))
    )
    (net (code "72") (name "unconnected-(J6-Pad3)") (class "Default")
      (node (ref "J6") (pin "3") (pinfunction "3_3") (pintype "passive"))
    )
    (net (code "73") (name "unconnected-(J6-Pad4)") (class "Default")
      (node (ref "J6") (pin "4") (pinfunction "4_4") (pintype "passive"))
    )
  )
)
